# Game_of_Life_Colour.net
KiCad netlist of a schematic drawn in EAGLE
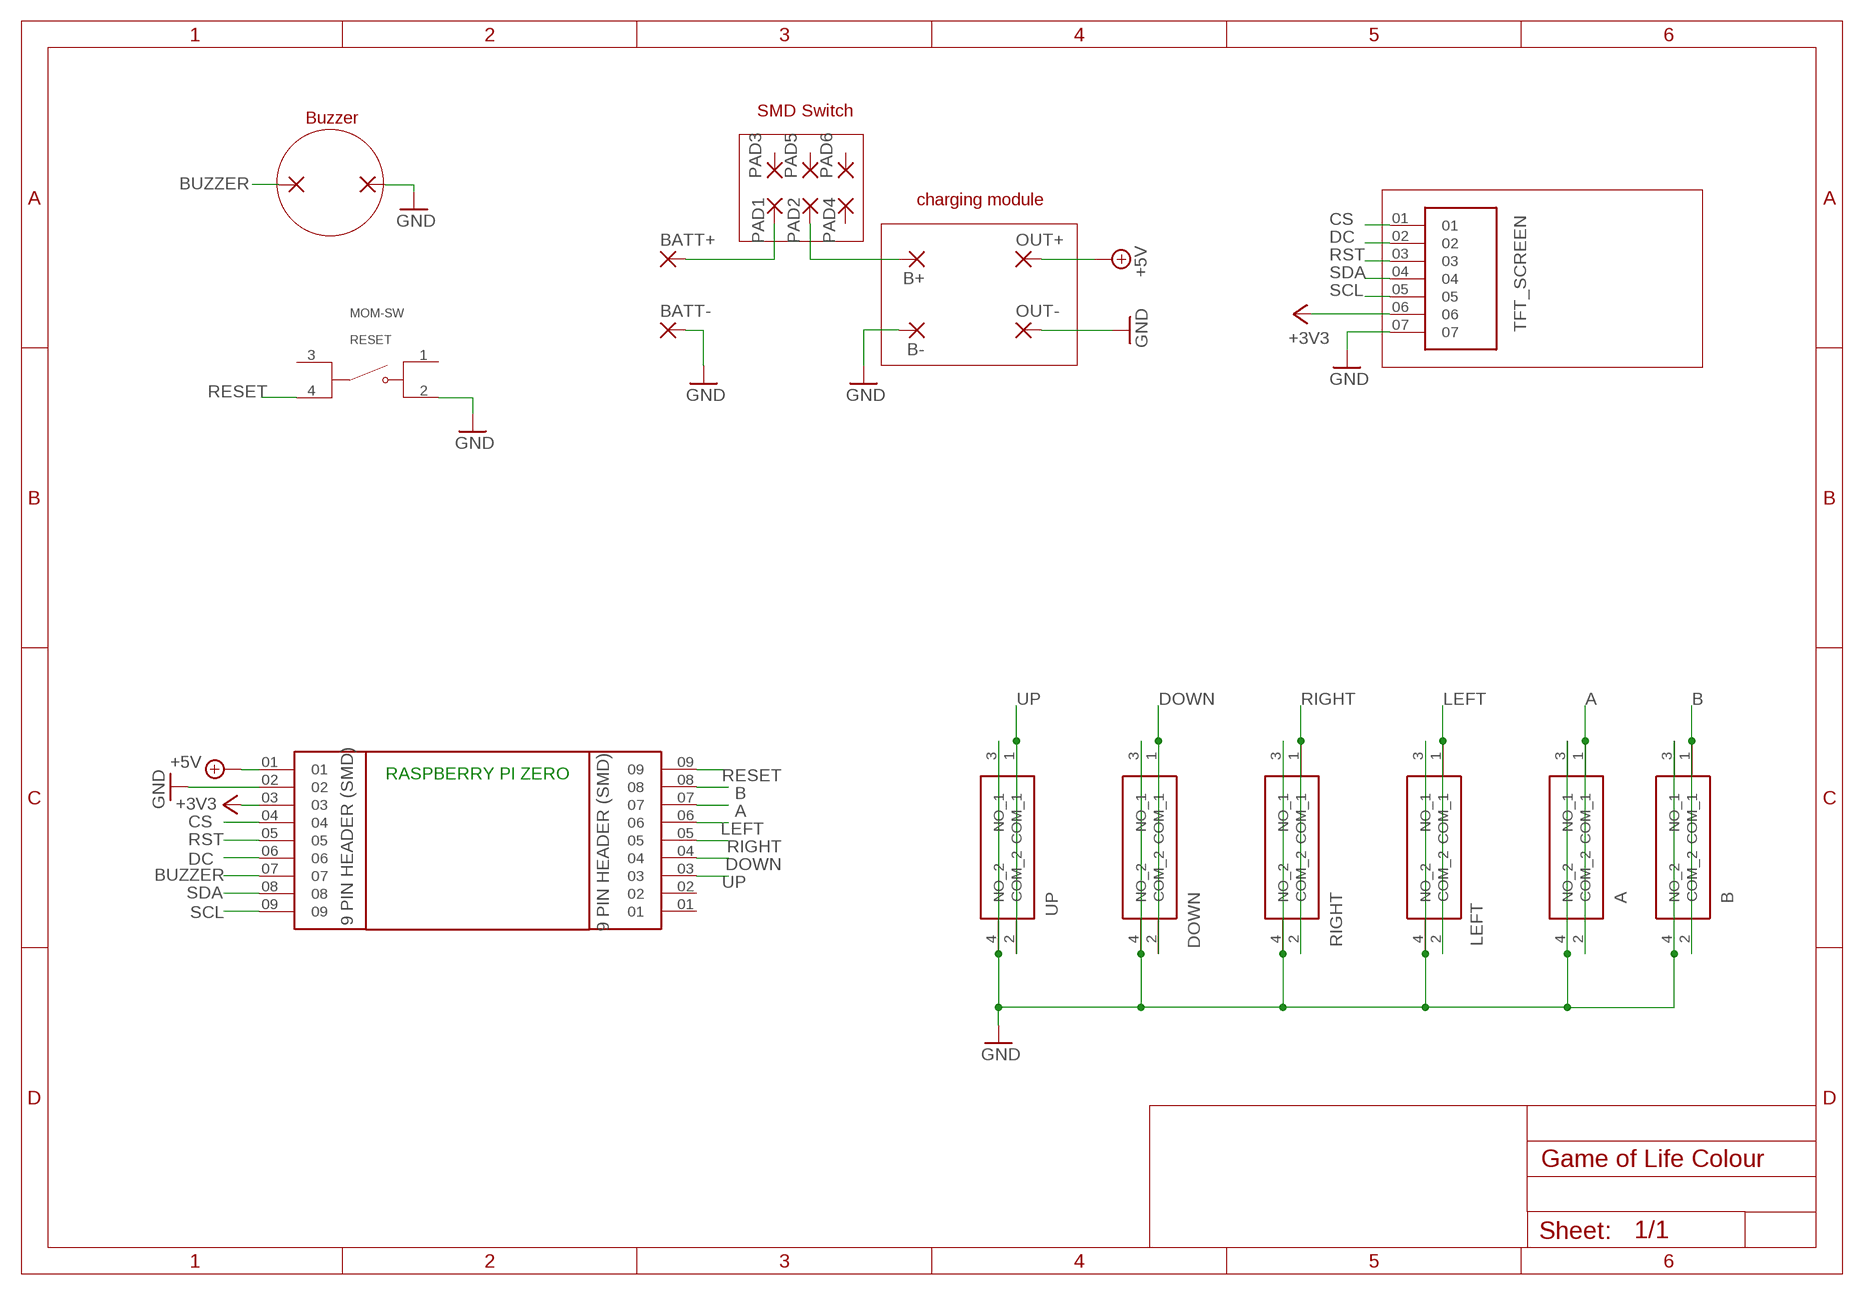
[diagram p0: schematic, sheet 1]

(export (version "E")
  (design (tool "Eeschema 10.0.6"))
  (components
    (comp (ref "A")
      (value "101-0364-EV")
      (footprint "eagle-import:1010364EV")
      (libsource (lib "eagle-import") (part "101-0364-EV"))
    )
    (comp (ref "B")
      (value "101-0364-EV")
      (footprint "eagle-import:1010364EV")
      (libsource (lib "eagle-import") (part "101-0364-EV"))
    )
    (comp (ref "B+")
      (value "SMD5")
      (footprint "eagle-import:SMD2,54-5,08")
      (libsource (lib "eagle-import") (part "SMD5"))
    )
    (comp (ref "B-")
      (value "SMD5")
      (footprint "eagle-import:SMD2,54-5,08")
      (libsource (lib "eagle-import") (part "SMD5"))
    )
    (comp (ref "BATT+")
      (value "SMD5")
      (footprint "eagle-import:SMD2,54-5,08")
      (libsource (lib "eagle-import") (part "SMD5"))
    )
    (comp (ref "BATT-")
      (value "SMD5")
      (footprint "eagle-import:SMD2,54-5,08")
      (libsource (lib "eagle-import") (part "SMD5"))
    )
    (comp (ref "DOWN")
      (value "101-0364-EV")
      (footprint "eagle-import:1010364EV")
      (libsource (lib "eagle-import") (part "101-0364-EV"))
    )
    (comp (ref "J2")
      (value "9 PIN HEADER (SMD)")
      (footprint "eagle-import:SAMTEC_TMM-108-X-X-S-SM")
      (fields (field (name "MF") "Samtec") (field (name "MP") "TMM-108-01-S-S-SM"))
      (libsource (lib "eagle-import") (part "9 Pin Header SMD_TMM-108-X-X-S-SM"))
    )
    (comp (ref "J3")
      (value "9 PIN HEADER (SMD)")
      (footprint "eagle-import:SAMTEC_TMM-108-X-X-S-SM")
      (fields (field (name "MF") "Samtec") (field (name "MP") "TMM-108-01-S-S-SM"))
      (libsource (lib "eagle-import") (part "9 Pin Header SMD_TMM-108-X-X-S-SM"))
    )
    (comp (ref "LEFT")
      (value "101-0364-EV")
      (footprint "eagle-import:1010364EV")
      (libsource (lib "eagle-import") (part "101-0364-EV"))
    )
    (comp (ref "OUT+")
      (value "SMD5")
      (footprint "eagle-import:SMD2,54-5,08")
      (libsource (lib "eagle-import") (part "SMD5"))
    )
    (comp (ref "OUT-")
      (value "SMD5")
      (footprint "eagle-import:SMD2,54-5,08")
      (libsource (lib "eagle-import") (part "SMD5"))
    )
    (comp (ref "PAD1")
      (value "SMD2")
      (footprint "eagle-import:SMD1,27-2,54")
      (libsource (lib "eagle-import") (part "SMD2"))
    )
    (comp (ref "PAD2")
      (value "SMD2")
      (footprint "eagle-import:SMD1,27-2,54")
      (libsource (lib "eagle-import") (part "SMD2"))
    )
    (comp (ref "PAD3")
      (value "SMD2")
      (footprint "eagle-import:SMD1,27-2,54")
      (libsource (lib "eagle-import") (part "SMD2"))
    )
    (comp (ref "PAD4")
      (value "SMD2")
      (footprint "eagle-import:SMD1,27-2,54")
      (libsource (lib "eagle-import") (part "SMD2"))
    )
    (comp (ref "PAD5")
      (value "SMD2")
      (footprint "eagle-import:SMD1,27-2,54")
      (libsource (lib "eagle-import") (part "SMD2"))
    )
    (comp (ref "PAD6")
      (value "SMD2")
      (footprint "eagle-import:SMD1,27-2,54")
      (libsource (lib "eagle-import") (part "SMD2"))
    )
    (comp (ref "PAD7")
      (value "SMD2")
      (footprint "eagle-import:SMD1,27-2,54")
      (libsource (lib "eagle-import") (part "SMD2"))
    )
    (comp (ref "PAD8")
      (value "SMD2")
      (footprint "eagle-import:SMD1,27-2,54")
      (libsource (lib "eagle-import") (part "SMD2"))
    )
    (comp (ref "RESET")
      (value "MOM-SW")
      (footprint "eagle-import:SW_TS18-5-25-SL-260-SMT-TR")
      (fields (field (name "MF") "Same Sky") (field (name "MP") "TS18-5-25-SL-260-SMT-TR"))
      (libsource (lib "eagle-import") (part "TS18-5-25-SL-260-SMT-TR"))
    )
    (comp (ref "RIGHT")
      (value "101-0364-EV")
      (footprint "eagle-import:1010364EV")
      (libsource (lib "eagle-import") (part "101-0364-EV"))
    )
    (comp (ref "TFT_SCREEN")
      (value "TMM-108-X-X-S-SM")
      (footprint "eagle-import:SAMTEC_TMM-108-X-X-S-SM")
      (fields (field (name "MF") "Samtec") (field (name "MP") "TMM-108-01-S-S-SM"))
      (libsource (lib "eagle-import") (part "TMM-108-X-X-S-SM"))
    )
    (comp (ref "UP")
      (value "101-0364-EV")
      (footprint "eagle-import:1010364EV")
      (libsource (lib "eagle-import") (part "101-0364-EV"))
    )
  )
  (nets
    (net (code "1") (name "+3V3") (class "Default")
      (node (ref "J3") (pin "03") (pinfunction "03_03") (pintype "passive"))
      (node (ref "TFT_SCREEN") (pin "06") (pinfunction "06_06") (pintype "passive"))
    )
    (net (code "2") (name "+5V") (class "Default")
      (node (ref "J3") (pin "01") (pinfunction "01_01") (pintype "passive"))
      (node (ref "OUT+") (pin "1") (pinfunction "P_1") (pintype "passive"))
    )
    (net (code "3") (name "/A") (class "Default")
      (node (ref "A") (pin "1") (pinfunction "COM_1_1") (pintype "bidirectional"))
      (node (ref "A") (pin "2") (pinfunction "COM_2_2") (pintype "bidirectional"))
      (node (ref "J2") (pin "07") (pinfunction "07_07") (pintype "passive"))
    )
    (net (code "4") (name "/B") (class "Default")
      (node (ref "B") (pin "1") (pinfunction "COM_1_1") (pintype "bidirectional"))
      (node (ref "B") (pin "2") (pinfunction "COM_2_2") (pintype "bidirectional"))
      (node (ref "J2") (pin "08") (pinfunction "08_08") (pintype "passive"))
    )
    (net (code "5") (name "/BUZZER") (class "Default")
      (node (ref "J3") (pin "07") (pinfunction "07_07") (pintype "passive"))
      (node (ref "PAD7") (pin "1") (pinfunction "P_1") (pintype "passive"))
    )
    (net (code "6") (name "/CS") (class "Default")
      (node (ref "J3") (pin "04") (pinfunction "04_04") (pintype "passive"))
      (node (ref "TFT_SCREEN") (pin "01") (pinfunction "01_01") (pintype "passive"))
    )
    (net (code "7") (name "/DC") (class "Default")
      (node (ref "J3") (pin "06") (pinfunction "06_06") (pintype "passive"))
      (node (ref "TFT_SCREEN") (pin "02") (pinfunction "02_02") (pintype "passive"))
    )
    (net (code "8") (name "/DOWN") (class "Default")
      (node (ref "DOWN") (pin "1") (pinfunction "COM_1_1") (pintype "bidirectional"))
      (node (ref "DOWN") (pin "2") (pinfunction "COM_2_2") (pintype "bidirectional"))
      (node (ref "J2") (pin "04") (pinfunction "04_04") (pintype "passive"))
    )
    (net (code "9") (name "/LEFT") (class "Default")
      (node (ref "J2") (pin "06") (pinfunction "06_06") (pintype "passive"))
      (node (ref "LEFT") (pin "1") (pinfunction "COM_1_1") (pintype "bidirectional"))
      (node (ref "LEFT") (pin "2") (pinfunction "COM_2_2") (pintype "bidirectional"))
    )
    (net (code "10") (name "/RESET") (class "Default")
      (node (ref "J2") (pin "09") (pinfunction "09_09") (pintype "passive"))
      (node (ref "RESET") (pin "4") (pinfunction "4_4") (pintype "passive"))
    )
    (net (code "11") (name "/RIGHT") (class "Default")
      (node (ref "J2") (pin "05") (pinfunction "05_05") (pintype "passive"))
      (node (ref "RIGHT") (pin "1") (pinfunction "COM_1_1") (pintype "bidirectional"))
      (node (ref "RIGHT") (pin "2") (pinfunction "COM_2_2") (pintype "bidirectional"))
    )
    (net (code "12") (name "/RST") (class "Default")
      (node (ref "J3") (pin "05") (pinfunction "05_05") (pintype "passive"))
      (node (ref "TFT_SCREEN") (pin "03") (pinfunction "03_03") (pintype "passive"))
    )
    (net (code "13") (name "/SCL") (class "Default")
      (node (ref "J3") (pin "09") (pinfunction "09_09") (pintype "passive"))
      (node (ref "TFT_SCREEN") (pin "05") (pinfunction "05_05") (pintype "passive"))
    )
    (net (code "14") (name "/SDA") (class "Default")
      (node (ref "J3") (pin "08") (pinfunction "08_08") (pintype "passive"))
      (node (ref "TFT_SCREEN") (pin "04") (pinfunction "04_04") (pintype "passive"))
    )
    (net (code "15") (name "/UP") (class "Default")
      (node (ref "J2") (pin "03") (pinfunction "03_03") (pintype "passive"))
      (node (ref "UP") (pin "1") (pinfunction "COM_1_1") (pintype "bidirectional"))
      (node (ref "UP") (pin "2") (pinfunction "COM_2_2") (pintype "bidirectional"))
    )
    (net (code "16") (name "GND") (class "Default")
      (node (ref "A") (pin "3") (pinfunction "NO_1_3") (pintype "bidirectional"))
      (node (ref "A") (pin "4") (pinfunction "NO_2_4") (pintype "bidirectional"))
      (node (ref "B") (pin "3") (pinfunction "NO_1_3") (pintype "bidirectional"))
      (node (ref "B") (pin "4") (pinfunction "NO_2_4") (pintype "bidirectional"))
      (node (ref "B-") (pin "1") (pinfunction "P_1") (pintype "passive"))
      (node (ref "BATT-") (pin "1") (pinfunction "P_1") (pintype "passive"))
      (node (ref "DOWN") (pin "3") (pinfunction "NO_1_3") (pintype "bidirectional"))
      (node (ref "DOWN") (pin "4") (pinfunction "NO_2_4") (pintype "bidirectional"))
      (node (ref "J3") (pin "02") (pinfunction "02_02") (pintype "passive"))
      (node (ref "LEFT") (pin "3") (pinfunction "NO_1_3") (pintype "bidirectional"))
      (node (ref "LEFT") (pin "4") (pinfunction "NO_2_4") (pintype "bidirectional"))
      (node (ref "OUT-") (pin "1") (pinfunction "P_1") (pintype "passive"))
      (node (ref "PAD8") (pin "1") (pinfunction "P_1") (pintype "passive"))
      (node (ref "RESET") (pin "2") (pinfunction "2_2") (pintype "passive"))
      (node (ref "RIGHT") (pin "3") (pinfunction "NO_1_3") (pintype "bidirectional"))
      (node (ref "RIGHT") (pin "4") (pinfunction "NO_2_4") (pintype "bidirectional"))
      (node (ref "TFT_SCREEN") (pin "07") (pinfunction "07_07") (pintype "passive"))
      (node (ref "UP") (pin "3") (pinfunction "NO_1_3") (pintype "bidirectional"))
      (node (ref "UP") (pin "4") (pinfunction "NO_2_4") (pintype "bidirectional"))
    )
    (net (code "17") (name "Net-(B+-P)") (class "Default")
      (node (ref "B+") (pin "1") (pinfunction "P_1") (pintype "passive"))
      (node (ref "PAD2") (pin "1") (pinfunction "P_1") (pintype "passive"))
    )
    (net (code "18") (name "Net-(BATT+-P)") (class "Default")
      (node (ref "BATT+") (pin "1") (pinfunction "P_1") (pintype "passive"))
      (node (ref "PAD1") (pin "1") (pinfunction "P_1") (pintype "passive"))
    )
    (net (code "19") (name "unconnected-(J2-Pad01)") (class "Default")
      (node (ref "J2") (pin "01") (pinfunction "01_01") (pintype "passive"))
    )
    (net (code "20") (name "unconnected-(J2-Pad02)") (class "Default")
      (node (ref "J2") (pin "02") (pinfunction "02_02") (pintype "passive"))
    )
    (net (code "21") (name "unconnected-(PAD3-P-Pad1)") (class "Default")
      (node (ref "PAD3") (pin "1") (pinfunction "P_1") (pintype "passive"))
    )
    (net (code "22") (name "unconnected-(PAD4-P-Pad1)") (class "Default")
      (node (ref "PAD4") (pin "1") (pinfunction "P_1") (pintype "passive"))
    )
    (net (code "23") (name "unconnected-(PAD5-P-Pad1)") (class "Default")
      (node (ref "PAD5") (pin "1") (pinfunction "P_1") (pintype "passive"))
    )
    (net (code "24") (name "unconnected-(PAD6-P-Pad1)") (class "Default")
      (node (ref "PAD6") (pin "1") (pinfunction "P_1") (pintype "passive"))
    )
    (net (code "25") (name "unconnected-(RESET-Pad1)") (class "Default")
      (node (ref "RESET") (pin "1") (pinfunction "1_1") (pintype "passive"))
    )
    (net (code "26") (name "unconnected-(RESET-Pad3)") (class "Default")
      (node (ref "RESET") (pin "3") (pinfunction "3_3") (pintype "passive"))
    )
  )
)
